# EMMC.net
KiCad netlist of a schematic drawn in Altium Designer
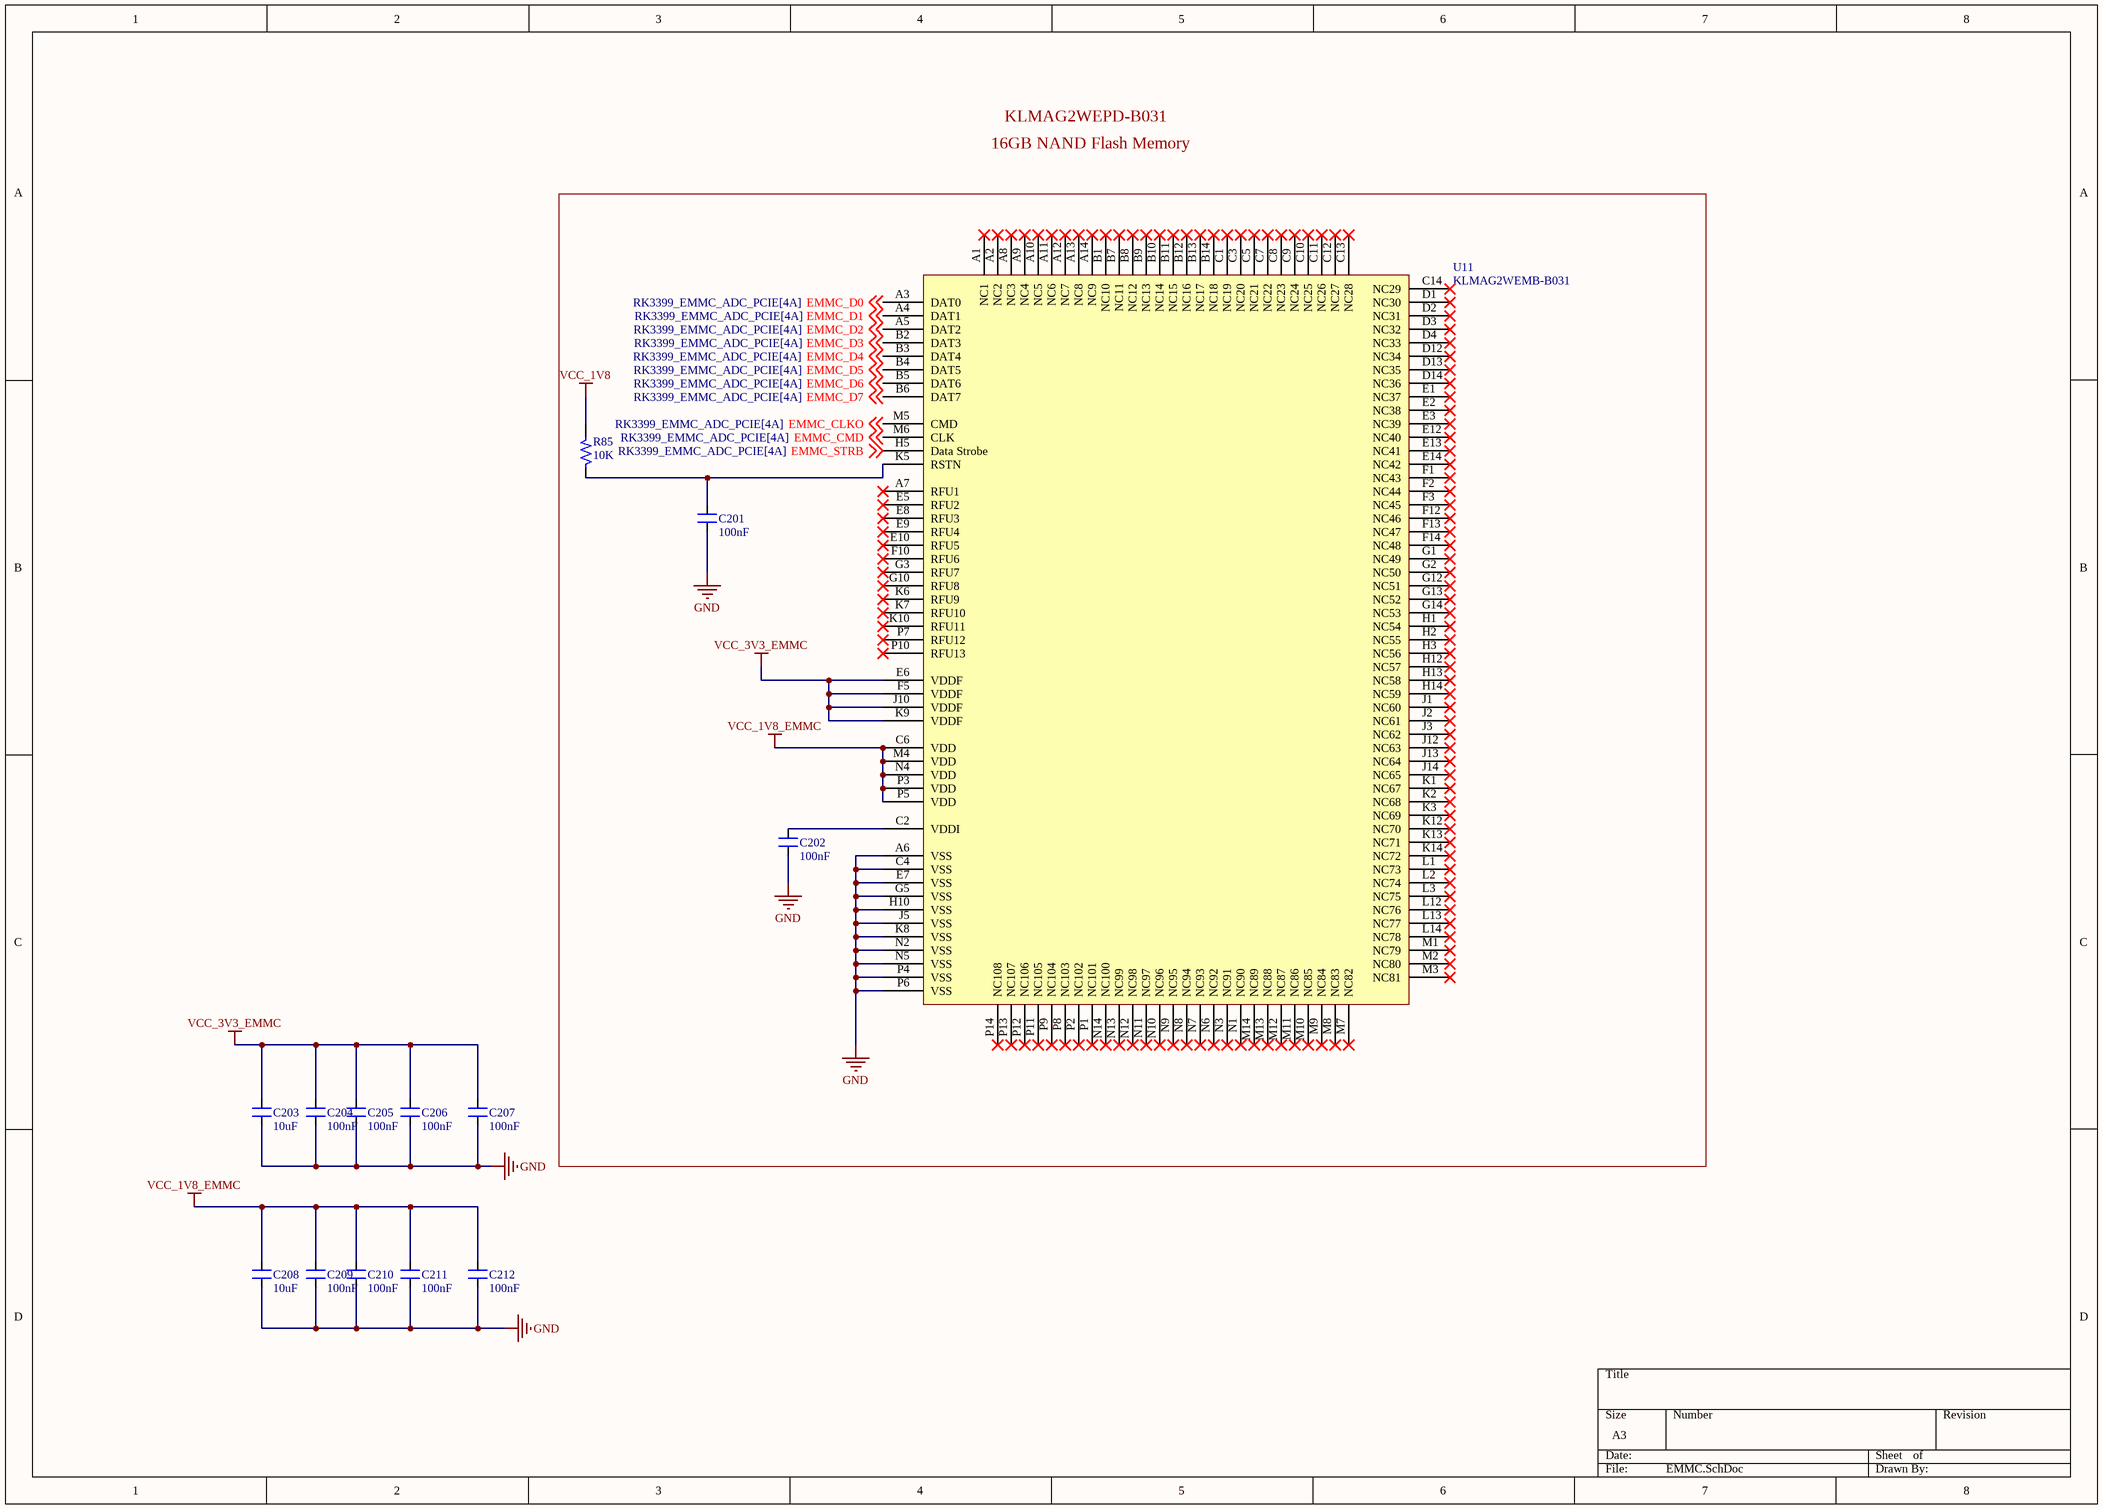
[diagram p0: EMMC.SchDoc]

(export (version "E")
  (design (tool "Eeschema 10.0.6"))
  (components
    (comp (ref "C201")
      (value "100nF")
      (footprint "CAP_0201")
      (description "0.1µF ±10% 25V Ceramic Capacitor X5R 0201 (0603 Metric)")
      (fields
        (field (name "MANUFACTURER") "TDK Corporation")
        (field (name "MANUFACTURER PART NUMBER") "C0603X5R1E104K030BB")
      )
      (libsource (lib "EsteemPCB_SOM_Course_schlib") (part "CAP_100nF-25V-10%-0201"))
    )
    (comp (ref "C202")
      (value "100nF")
      (footprint "CAP_0201")
      (description "0.1µF ±10% 25V Ceramic Capacitor X5R 0201 (0603 Metric)")
      (fields
        (field (name "MANUFACTURER") "TDK Corporation")
        (field (name "MANUFACTURER PART NUMBER") "C0603X5R1E104K030BB")
      )
      (libsource (lib "EsteemPCB_SOM_Course_schlib") (part "CAP_100nF-25V-10%-0201"))
    )
    (comp (ref "C203")
      (value "10uF")
      (footprint "CAP_0603")
      (description "10µF ±10% 10V Ceramic Capacitor X5R 0603 (1608 Metric)")
      (fields
        (field (name "MANUFACTURER PART NUMBER") "GRM188R61A106KE69J")
        (field (name "MANUFACTURER") "Murata Electronics")
      )
      (libsource (lib "EsteemPCB_SOM_Course_schlib") (part "CAP_10uF-10V-10%-0603"))
    )
    (comp (ref "C204")
      (value "100nF")
      (footprint "CAP_0201")
      (description "0.1µF ±10% 25V Ceramic Capacitor X5R 0201 (0603 Metric)")
      (fields
        (field (name "MANUFACTURER") "TDK Corporation")
        (field (name "MANUFACTURER PART NUMBER") "C0603X5R1E104K030BB")
      )
      (libsource (lib "EsteemPCB_SOM_Course_schlib") (part "CAP_100nF-25V-10%-0201"))
    )
    (comp (ref "C205")
      (value "100nF")
      (footprint "CAP_0201")
      (description "0.1µF ±10% 25V Ceramic Capacitor X5R 0201 (0603 Metric)")
      (fields
        (field (name "MANUFACTURER") "TDK Corporation")
        (field (name "MANUFACTURER PART NUMBER") "C0603X5R1E104K030BB")
      )
      (libsource (lib "EsteemPCB_SOM_Course_schlib") (part "CAP_100nF-25V-10%-0201"))
    )
    (comp (ref "C206")
      (value "100nF")
      (footprint "CAP_0201")
      (description "0.1µF ±10% 25V Ceramic Capacitor X5R 0201 (0603 Metric)")
      (fields
        (field (name "MANUFACTURER") "TDK Corporation")
        (field (name "MANUFACTURER PART NUMBER") "C0603X5R1E104K030BB")
      )
      (libsource (lib "EsteemPCB_SOM_Course_schlib") (part "CAP_100nF-25V-10%-0201"))
    )
    (comp (ref "C207")
      (value "100nF")
      (footprint "CAP_0201")
      (description "0.1µF ±10% 25V Ceramic Capacitor X5R 0201 (0603 Metric)")
      (fields
        (field (name "MANUFACTURER") "TDK Corporation")
        (field (name "MANUFACTURER PART NUMBER") "C0603X5R1E104K030BB")
      )
      (libsource (lib "EsteemPCB_SOM_Course_schlib") (part "CAP_100nF-25V-10%-0201"))
    )
    (comp (ref "C208")
      (value "10uF")
      (footprint "CAP_0603")
      (description "10µF ±10% 10V Ceramic Capacitor X5R 0603 (1608 Metric)")
      (fields
        (field (name "MANUFACTURER PART NUMBER") "GRM188R61A106KE69J")
        (field (name "MANUFACTURER") "Murata Electronics")
      )
      (libsource (lib "EsteemPCB_SOM_Course_schlib") (part "CAP_10uF-10V-10%-0603"))
    )
    (comp (ref "C209")
      (value "100nF")
      (footprint "CAP_0201")
      (description "0.1µF ±10% 25V Ceramic Capacitor X5R 0201 (0603 Metric)")
      (fields
        (field (name "MANUFACTURER") "TDK Corporation")
        (field (name "MANUFACTURER PART NUMBER") "C0603X5R1E104K030BB")
      )
      (libsource (lib "EsteemPCB_SOM_Course_schlib") (part "CAP_100nF-25V-10%-0201"))
    )
    (comp (ref "C210")
      (value "100nF")
      (footprint "CAP_0201")
      (description "0.1µF ±10% 25V Ceramic Capacitor X5R 0201 (0603 Metric)")
      (fields
        (field (name "MANUFACTURER") "TDK Corporation")
        (field (name "MANUFACTURER PART NUMBER") "C0603X5R1E104K030BB")
      )
      (libsource (lib "EsteemPCB_SOM_Course_schlib") (part "CAP_100nF-25V-10%-0201"))
    )
    (comp (ref "C211")
      (value "100nF")
      (footprint "CAP_0201")
      (description "0.1µF ±10% 25V Ceramic Capacitor X5R 0201 (0603 Metric)")
      (fields
        (field (name "MANUFACTURER") "TDK Corporation")
        (field (name "MANUFACTURER PART NUMBER") "C0603X5R1E104K030BB")
      )
      (libsource (lib "EsteemPCB_SOM_Course_schlib") (part "CAP_100nF-25V-10%-0201"))
    )
    (comp (ref "C212")
      (value "100nF")
      (footprint "CAP_0201")
      (description "0.1µF ±10% 25V Ceramic Capacitor X5R 0201 (0603 Metric)")
      (fields
        (field (name "MANUFACTURER") "TDK Corporation")
        (field (name "MANUFACTURER PART NUMBER") "C0603X5R1E104K030BB")
      )
      (libsource (lib "EsteemPCB_SOM_Course_schlib") (part "CAP_100nF-25V-10%-0201"))
    )
    (comp (ref "R85")
      (value "10K")
      (footprint "RES_0201")
      (description "10 kOhms ±1% 0.05W, 1/20W Chip Resistor 0201 (0603 Metric) Thick Film")
      (fields
        (field (name "MANUFACTURER") "Stackpole Electronics Inc")
        (field (name "MANUFACTURER PART NUMBER") "RMCF0201FT10K0")
      )
      (libsource (lib "EsteemPCB_SOM_Course_schlib") (part "RES_10K-0.05W-1%-0201"))
    )
    (comp (ref "U11")
      (value "KLMAG2WEMB-B031")
      (footprint "BGA153C50P14X14_1150X1300X70")
      (description "16GB NAND Flash Memory")
      (fields (field (name "MANUFACTURER") "Samsung Electronics"))
      (libsource (lib "EsteemPCB_SOM_Course_schlib") (part "IC_KLMAG2WEMB-B031"))
    )
  )
  (nets
    (net (code "1") (name "EMMC_CLKO") (class "Default")
      (node (ref "U11") (pin "M5") (pinfunction "CMD_M5") (pintype "passive"))
    )
    (net (code "2") (name "EMMC_CMD") (class "Default")
      (node (ref "U11") (pin "M6") (pinfunction "CLK_M6") (pintype "passive"))
    )
    (net (code "3") (name "EMMC_D0") (class "Default")
      (node (ref "U11") (pin "A3") (pinfunction "DAT0_A3") (pintype "passive"))
    )
    (net (code "4") (name "EMMC_D1") (class "Default")
      (node (ref "U11") (pin "A4") (pinfunction "DAT1_A4") (pintype "passive"))
    )
    (net (code "5") (name "EMMC_D2") (class "Default")
      (node (ref "U11") (pin "A5") (pinfunction "DAT2_A5") (pintype "passive"))
    )
    (net (code "6") (name "EMMC_D3") (class "Default")
      (node (ref "U11") (pin "B2") (pinfunction "DAT3_B2") (pintype "passive"))
    )
    (net (code "7") (name "EMMC_D4") (class "Default")
      (node (ref "U11") (pin "B3") (pinfunction "DAT4_B3") (pintype "passive"))
    )
    (net (code "8") (name "EMMC_D5") (class "Default")
      (node (ref "U11") (pin "B4") (pinfunction "DAT5_B4") (pintype "passive"))
    )
    (net (code "9") (name "EMMC_D6") (class "Default")
      (node (ref "U11") (pin "B5") (pinfunction "DAT6_B5") (pintype "passive"))
    )
    (net (code "10") (name "EMMC_D7") (class "Default")
      (node (ref "U11") (pin "B6") (pinfunction "DAT7_B6") (pintype "passive"))
    )
    (net (code "11") (name "EMMC_STRB") (class "Default")
      (node (ref "U11") (pin "H5") (pinfunction "Data_Strobe_H5") (pintype "passive"))
    )
    (net (code "12") (name "GND") (class "Default")
      (node (ref "C201") (pin "2") (pinfunction "2_2") (pintype "passive"))
      (node (ref "C202") (pin "2") (pinfunction "2_2") (pintype "passive"))
      (node (ref "C203") (pin "1") (pinfunction "1_1") (pintype "passive"))
      (node (ref "C204") (pin "2") (pinfunction "2_2") (pintype "passive"))
      (node (ref "C205") (pin "2") (pinfunction "2_2") (pintype "passive"))
      (node (ref "C206") (pin "2") (pinfunction "2_2") (pintype "passive"))
      (node (ref "C207") (pin "2") (pinfunction "2_2") (pintype "passive"))
      (node (ref "C208") (pin "1") (pinfunction "1_1") (pintype "passive"))
      (node (ref "C209") (pin "2") (pinfunction "2_2") (pintype "passive"))
      (node (ref "C210") (pin "2") (pinfunction "2_2") (pintype "passive"))
      (node (ref "C211") (pin "2") (pinfunction "2_2") (pintype "passive"))
      (node (ref "C212") (pin "2") (pinfunction "2_2") (pintype "passive"))
      (node (ref "U11") (pin "A6") (pinfunction "VSS_A6") (pintype "passive"))
      (node (ref "U11") (pin "C4") (pinfunction "VSS_C4") (pintype "passive"))
      (node (ref "U11") (pin "E7") (pinfunction "VSS_E7") (pintype "passive"))
      (node (ref "U11") (pin "G5") (pinfunction "VSS_G5") (pintype "passive"))
      (node (ref "U11") (pin "H10") (pinfunction "VSS_H10") (pintype "passive"))
      (node (ref "U11") (pin "J5") (pinfunction "VSS_J5") (pintype "passive"))
      (node (ref "U11") (pin "K8") (pinfunction "VSS_K8") (pintype "passive"))
      (node (ref "U11") (pin "N2") (pinfunction "VSS_N2") (pintype "passive"))
      (node (ref "U11") (pin "N5") (pinfunction "VSS_N5") (pintype "passive"))
      (node (ref "U11") (pin "P4") (pinfunction "VSS_P4") (pintype "passive"))
      (node (ref "U11") (pin "P6") (pinfunction "VSS_P6") (pintype "passive"))
    )
    (net (code "13") (name "Net-(U11-RSTN)") (class "Default")
      (node (ref "C201") (pin "1") (pinfunction "1_1") (pintype "passive"))
      (node (ref "R85") (pin "1") (pinfunction "1_1") (pintype "passive"))
      (node (ref "U11") (pin "K5") (pinfunction "RSTN_K5") (pintype "passive"))
    )
    (net (code "14") (name "Net-(U11-VDDI)") (class "Default")
      (node (ref "C202") (pin "1") (pinfunction "1_1") (pintype "passive"))
      (node (ref "U11") (pin "C2") (pinfunction "VDDI_C2") (pintype "passive"))
    )
    (net (code "15") (name "VCC_1V8") (class "Default")
      (node (ref "R85") (pin "2") (pinfunction "2_2") (pintype "passive"))
    )
    (net (code "16") (name "VCC_1V8_EMMC") (class "Default")
      (node (ref "C208") (pin "2") (pinfunction "2_2") (pintype "passive"))
      (node (ref "C209") (pin "1") (pinfunction "1_1") (pintype "passive"))
      (node (ref "C210") (pin "1") (pinfunction "1_1") (pintype "passive"))
      (node (ref "C211") (pin "1") (pinfunction "1_1") (pintype "passive"))
      (node (ref "C212") (pin "1") (pinfunction "1_1") (pintype "passive"))
      (node (ref "U11") (pin "C6") (pinfunction "VDD_C6") (pintype "passive"))
      (node (ref "U11") (pin "M4") (pinfunction "VDD_M4") (pintype "passive"))
      (node (ref "U11") (pin "N4") (pinfunction "VDD_N4") (pintype "passive"))
      (node (ref "U11") (pin "P3") (pinfunction "VDD_P3") (pintype "passive"))
      (node (ref "U11") (pin "P5") (pinfunction "VDD_P5") (pintype "passive"))
    )
    (net (code "17") (name "VCC_3V3_EMMC") (class "Default")
      (node (ref "C203") (pin "2") (pinfunction "2_2") (pintype "passive"))
      (node (ref "C204") (pin "1") (pinfunction "1_1") (pintype "passive"))
      (node (ref "C205") (pin "1") (pinfunction "1_1") (pintype "passive"))
      (node (ref "C206") (pin "1") (pinfunction "1_1") (pintype "passive"))
      (node (ref "C207") (pin "1") (pinfunction "1_1") (pintype "passive"))
      (node (ref "U11") (pin "E6") (pinfunction "VDDF_E6") (pintype "passive"))
      (node (ref "U11") (pin "F5") (pinfunction "VDDF_F5") (pintype "passive"))
      (node (ref "U11") (pin "J10") (pinfunction "VDDF_J10") (pintype "passive"))
      (node (ref "U11") (pin "K9") (pinfunction "VDDF_K9") (pintype "passive"))
    )
    (net (code "18") (name "unconnected-(U11-NC1-PadA1)") (class "Default")
      (node (ref "U11") (pin "A1") (pinfunction "NC1_A1") (pintype "passive+no_connect"))
    )
    (net (code "19") (name "unconnected-(U11-NC2-PadA2)") (class "Default")
      (node (ref "U11") (pin "A2") (pinfunction "NC2_A2") (pintype "passive+no_connect"))
    )
    (net (code "20") (name "unconnected-(U11-NC3-PadA8)") (class "Default")
      (node (ref "U11") (pin "A8") (pinfunction "NC3_A8") (pintype "passive+no_connect"))
    )
    (net (code "21") (name "unconnected-(U11-NC4-PadA9)") (class "Default")
      (node (ref "U11") (pin "A9") (pinfunction "NC4_A9") (pintype "passive+no_connect"))
    )
    (net (code "22") (name "unconnected-(U11-NC5-PadA10)") (class "Default")
      (node (ref "U11") (pin "A10") (pinfunction "NC5_A10") (pintype "passive+no_connect"))
    )
    (net (code "23") (name "unconnected-(U11-NC6-PadA11)") (class "Default")
      (node (ref "U11") (pin "A11") (pinfunction "NC6_A11") (pintype "passive+no_connect"))
    )
    (net (code "24") (name "unconnected-(U11-NC7-PadA12)") (class "Default")
      (node (ref "U11") (pin "A12") (pinfunction "NC7_A12") (pintype "passive+no_connect"))
    )
    (net (code "25") (name "unconnected-(U11-NC8-PadA13)") (class "Default")
      (node (ref "U11") (pin "A13") (pinfunction "NC8_A13") (pintype "passive+no_connect"))
    )
    (net (code "26") (name "unconnected-(U11-NC9-PadA14)") (class "Default")
      (node (ref "U11") (pin "A14") (pinfunction "NC9_A14") (pintype "passive+no_connect"))
    )
    (net (code "27") (name "unconnected-(U11-NC10-PadB1)") (class "Default")
      (node (ref "U11") (pin "B1") (pinfunction "NC10_B1") (pintype "passive+no_connect"))
    )
    (net (code "28") (name "unconnected-(U11-NC11-PadB7)") (class "Default")
      (node (ref "U11") (pin "B7") (pinfunction "NC11_B7") (pintype "passive+no_connect"))
    )
    (net (code "29") (name "unconnected-(U11-NC12-PadB8)") (class "Default")
      (node (ref "U11") (pin "B8") (pinfunction "NC12_B8") (pintype "passive+no_connect"))
    )
    (net (code "30") (name "unconnected-(U11-NC13-PadB9)") (class "Default")
      (node (ref "U11") (pin "B9") (pinfunction "NC13_B9") (pintype "passive+no_connect"))
    )
    (net (code "31") (name "unconnected-(U11-NC14-PadB10)") (class "Default")
      (node (ref "U11") (pin "B10") (pinfunction "NC14_B10") (pintype "passive+no_connect"))
    )
    (net (code "32") (name "unconnected-(U11-NC15-PadB11)") (class "Default")
      (node (ref "U11") (pin "B11") (pinfunction "NC15_B11") (pintype "passive+no_connect"))
    )
    (net (code "33") (name "unconnected-(U11-NC16-PadB12)") (class "Default")
      (node (ref "U11") (pin "B12") (pinfunction "NC16_B12") (pintype "passive+no_connect"))
    )
    (net (code "34") (name "unconnected-(U11-NC17-PadB13)") (class "Default")
      (node (ref "U11") (pin "B13") (pinfunction "NC17_B13") (pintype "passive+no_connect"))
    )
    (net (code "35") (name "unconnected-(U11-NC18-PadB14)") (class "Default")
      (node (ref "U11") (pin "B14") (pinfunction "NC18_B14") (pintype "passive+no_connect"))
    )
    (net (code "36") (name "unconnected-(U11-NC19-PadC1)") (class "Default")
      (node (ref "U11") (pin "C1") (pinfunction "NC19_C1") (pintype "passive+no_connect"))
    )
    (net (code "37") (name "unconnected-(U11-NC20-PadC3)") (class "Default")
      (node (ref "U11") (pin "C3") (pinfunction "NC20_C3") (pintype "passive+no_connect"))
    )
    (net (code "38") (name "unconnected-(U11-NC21-PadC5)") (class "Default")
      (node (ref "U11") (pin "C5") (pinfunction "NC21_C5") (pintype "passive+no_connect"))
    )
    (net (code "39") (name "unconnected-(U11-NC22-PadC7)") (class "Default")
      (node (ref "U11") (pin "C7") (pinfunction "NC22_C7") (pintype "passive+no_connect"))
    )
    (net (code "40") (name "unconnected-(U11-NC23-PadC8)") (class "Default")
      (node (ref "U11") (pin "C8") (pinfunction "NC23_C8") (pintype "passive+no_connect"))
    )
    (net (code "41") (name "unconnected-(U11-NC24-PadC9)") (class "Default")
      (node (ref "U11") (pin "C9") (pinfunction "NC24_C9") (pintype "passive+no_connect"))
    )
    (net (code "42") (name "unconnected-(U11-NC25-PadC10)") (class "Default")
      (node (ref "U11") (pin "C10") (pinfunction "NC25_C10") (pintype "passive+no_connect"))
    )
    (net (code "43") (name "unconnected-(U11-NC26-PadC11)") (class "Default")
      (node (ref "U11") (pin "C11") (pinfunction "NC26_C11") (pintype "passive+no_connect"))
    )
    (net (code "44") (name "unconnected-(U11-NC27-PadC12)") (class "Default")
      (node (ref "U11") (pin "C12") (pinfunction "NC27_C12") (pintype "passive+no_connect"))
    )
    (net (code "45") (name "unconnected-(U11-NC28-PadC13)") (class "Default")
      (node (ref "U11") (pin "C13") (pinfunction "NC28_C13") (pintype "passive+no_connect"))
    )
    (net (code "46") (name "unconnected-(U11-NC29-PadC14)") (class "Default")
      (node (ref "U11") (pin "C14") (pinfunction "NC29_C14") (pintype "passive+no_connect"))
    )
    (net (code "47") (name "unconnected-(U11-NC30-PadD1)") (class "Default")
      (node (ref "U11") (pin "D1") (pinfunction "NC30_D1") (pintype "passive+no_connect"))
    )
    (net (code "48") (name "unconnected-(U11-NC31-PadD2)") (class "Default")
      (node (ref "U11") (pin "D2") (pinfunction "NC31_D2") (pintype "passive+no_connect"))
    )
    (net (code "49") (name "unconnected-(U11-NC32-PadD3)") (class "Default")
      (node (ref "U11") (pin "D3") (pinfunction "NC32_D3") (pintype "passive+no_connect"))
    )
    (net (code "50") (name "unconnected-(U11-NC33-PadD4)") (class "Default")
      (node (ref "U11") (pin "D4") (pinfunction "NC33_D4") (pintype "passive+no_connect"))
    )
    (net (code "51") (name "unconnected-(U11-NC34-PadD12)") (class "Default")
      (node (ref "U11") (pin "D12") (pinfunction "NC34_D12") (pintype "passive+no_connect"))
    )
    (net (code "52") (name "unconnected-(U11-NC35-PadD13)") (class "Default")
      (node (ref "U11") (pin "D13") (pinfunction "NC35_D13") (pintype "passive+no_connect"))
    )
    (net (code "53") (name "unconnected-(U11-NC36-PadD14)") (class "Default")
      (node (ref "U11") (pin "D14") (pinfunction "NC36_D14") (pintype "passive+no_connect"))
    )
    (net (code "54") (name "unconnected-(U11-NC37-PadE1)") (class "Default")
      (node (ref "U11") (pin "E1") (pinfunction "NC37_E1") (pintype "passive+no_connect"))
    )
    (net (code "55") (name "unconnected-(U11-NC38-PadE2)") (class "Default")
      (node (ref "U11") (pin "E2") (pinfunction "NC38_E2") (pintype "passive+no_connect"))
    )
    (net (code "56") (name "unconnected-(U11-NC39-PadE3)") (class "Default")
      (node (ref "U11") (pin "E3") (pinfunction "NC39_E3") (pintype "passive+no_connect"))
    )
    (net (code "57") (name "unconnected-(U11-NC40-PadE12)") (class "Default")
      (node (ref "U11") (pin "E12") (pinfunction "NC40_E12") (pintype "passive+no_connect"))
    )
    (net (code "58") (name "unconnected-(U11-NC41-PadE13)") (class "Default")
      (node (ref "U11") (pin "E13") (pinfunction "NC41_E13") (pintype "passive+no_connect"))
    )
    (net (code "59") (name "unconnected-(U11-NC42-PadE14)") (class "Default")
      (node (ref "U11") (pin "E14") (pinfunction "NC42_E14") (pintype "passive+no_connect"))
    )
    (net (code "60") (name "unconnected-(U11-NC43-PadF1)") (class "Default")
      (node (ref "U11") (pin "F1") (pinfunction "NC43_F1") (pintype "passive+no_connect"))
    )
    (net (code "61") (name "unconnected-(U11-NC44-PadF2)") (class "Default")
      (node (ref "U11") (pin "F2") (pinfunction "NC44_F2") (pintype "passive+no_connect"))
    )
    (net (code "62") (name "unconnected-(U11-NC45-PadF3)") (class "Default")
      (node (ref "U11") (pin "F3") (pinfunction "NC45_F3") (pintype "passive+no_connect"))
    )
    (net (code "63") (name "unconnected-(U11-NC46-PadF12)") (class "Default")
      (node (ref "U11") (pin "F12") (pinfunction "NC46_F12") (pintype "passive+no_connect"))
    )
    (net (code "64") (name "unconnected-(U11-NC47-PadF13)") (class "Default")
      (node (ref "U11") (pin "F13") (pinfunction "NC47_F13") (pintype "passive+no_connect"))
    )
    (net (code "65") (name "unconnected-(U11-NC48-PadF14)") (class "Default")
      (node (ref "U11") (pin "F14") (pinfunction "NC48_F14") (pintype "passive+no_connect"))
    )
    (net (code "66") (name "unconnected-(U11-NC49-PadG1)") (class "Default")
      (node (ref "U11") (pin "G1") (pinfunction "NC49_G1") (pintype "passive+no_connect"))
    )
    (net (code "67") (name "unconnected-(U11-NC50-PadG2)") (class "Default")
      (node (ref "U11") (pin "G2") (pinfunction "NC50_G2") (pintype "passive+no_connect"))
    )
    (net (code "68") (name "unconnected-(U11-NC51-PadG12)") (class "Default")
      (node (ref "U11") (pin "G12") (pinfunction "NC51_G12") (pintype "passive+no_connect"))
    )
    (net (code "69") (name "unconnected-(U11-NC52-PadG13)") (class "Default")
      (node (ref "U11") (pin "G13") (pinfunction "NC52_G13") (pintype "passive+no_connect"))
    )
    (net (code "70") (name "unconnected-(U11-NC53-PadG14)") (class "Default")
      (node (ref "U11") (pin "G14") (pinfunction "NC53_G14") (pintype "passive+no_connect"))
    )
    (net (code "71") (name "unconnected-(U11-NC54-PadH1)") (class "Default")
      (node (ref "U11") (pin "H1") (pinfunction "NC54_H1") (pintype "passive+no_connect"))
    )
    (net (code "72") (name "unconnected-(U11-NC55-PadH2)") (class "Default")
      (node (ref "U11") (pin "H2") (pinfunction "NC55_H2") (pintype "passive+no_connect"))
    )
    (net (code "73") (name "unconnected-(U11-NC56-PadH3)") (class "Default")
      (node (ref "U11") (pin "H3") (pinfunction "NC56_H3") (pintype "passive+no_connect"))
    )
    (net (code "74") (name "unconnected-(U11-NC57-PadH12)") (class "Default")
      (node (ref "U11") (pin "H12") (pinfunction "NC57_H12") (pintype "passive+no_connect"))
    )
    (net (code "75") (name "unconnected-(U11-NC58-PadH13)") (class "Default")
      (node (ref "U11") (pin "H13") (pinfunction "NC58_H13") (pintype "passive+no_connect"))
    )
    (net (code "76") (name "unconnected-(U11-NC59-PadH14)") (class "Default")
      (node (ref "U11") (pin "H14") (pinfunction "NC59_H14") (pintype "passive+no_connect"))
    )
    (net (code "77") (name "unconnected-(U11-NC60-PadJ1)") (class "Default")
      (node (ref "U11") (pin "J1") (pinfunction "NC60_J1") (pintype "passive+no_connect"))
    )
    (net (code "78") (name "unconnected-(U11-NC61-PadJ2)") (class "Default")
      (node (ref "U11") (pin "J2") (pinfunction "NC61_J2") (pintype "passive+no_connect"))
    )
    (net (code "79") (name "unconnected-(U11-NC62-PadJ3)") (class "Default")
      (node (ref "U11") (pin "J3") (pinfunction "NC62_J3") (pintype "passive+no_connect"))
    )
    (net (code "80") (name "unconnected-(U11-NC63-PadJ12)") (class "Default")
      (node (ref "U11") (pin "J12") (pinfunction "NC63_J12") (pintype "passive+no_connect"))
    )
    (net (code "81") (name "unconnected-(U11-NC64-PadJ13)") (class "Default")
      (node (ref "U11") (pin "J13") (pinfunction "NC64_J13") (pintype "passive+no_connect"))
    )
    (net (code "82") (name "unconnected-(U11-NC65-PadJ14)") (class "Default")
      (node (ref "U11") (pin "J14") (pinfunction "NC65_J14") (pintype "passive+no_connect"))
    )
    (net (code "83") (name "unconnected-(U11-NC67-PadK1)") (class "Default")
      (node (ref "U11") (pin "K1") (pinfunction "NC67_K1") (pintype "passive+no_connect"))
    )
    (net (code "84") (name "unconnected-(U11-NC68-PadK2)") (class "Default")
      (node (ref "U11") (pin "K2") (pinfunction "NC68_K2") (pintype "passive+no_connect"))
    )
    (net (code "85") (name "unconnected-(U11-NC69-PadK3)") (class "Default")
      (node (ref "U11") (pin "K3") (pinfunction "NC69_K3") (pintype "passive+no_connect"))
    )
    (net (code "86") (name "unconnected-(U11-NC70-PadK12)") (class "Default")
      (node (ref "U11") (pin "K12") (pinfunction "NC70_K12") (pintype "passive+no_connect"))
    )
    (net (code "87") (name "unconnected-(U11-NC71-PadK13)") (class "Default")
      (node (ref "U11") (pin "K13") (pinfunction "NC71_K13") (pintype "passive+no_connect"))
    )
    (net (code "88") (name "unconnected-(U11-NC72-PadK14)") (class "Default")
      (node (ref "U11") (pin "K14") (pinfunction "NC72_K14") (pintype "passive+no_connect"))
    )
    (net (code "89") (name "unconnected-(U11-NC73-PadL1)") (class "Default")
      (node (ref "U11") (pin "L1") (pinfunction "NC73_L1") (pintype "passive+no_connect"))
    )
    (net (code "90") (name "unconnected-(U11-NC74-PadL2)") (class "Default")
      (node (ref "U11") (pin "L2") (pinfunction "NC74_L2") (pintype "passive+no_connect"))
    )
    (net (code "91") (name "unconnected-(U11-NC75-PadL3)") (class "Default")
      (node (ref "U11") (pin "L3") (pinfunction "NC75_L3") (pintype "passive+no_connect"))
    )
    (net (code "92") (name "unconnected-(U11-NC76-PadL12)") (class "Default")
      (node (ref "U11") (pin "L12") (pinfunction "NC76_L12") (pintype "passive+no_connect"))
    )
    (net (code "93") (name "unconnected-(U11-NC77-PadL13)") (class "Default")
      (node (ref "U11") (pin "L13") (pinfunction "NC77_L13") (pintype "passive+no_connect"))
    )
    (net (code "94") (name "unconnected-(U11-NC78-PadL14)") (class "Default")
      (node (ref "U11") (pin "L14") (pinfunction "NC78_L14") (pintype "passive+no_connect"))
    )
    (net (code "95") (name "unconnected-(U11-NC79-PadM1)") (class "Default")
      (node (ref "U11") (pin "M1") (pinfunction "NC79_M1") (pintype "passive+no_connect"))
    )
    (net (code "96") (name "unconnected-(U11-NC80-PadM2)") (class "Default")
      (node (ref "U11") (pin "M2") (pinfunction "NC80_M2") (pintype "passive+no_connect"))
    )
    (net (code "97") (name "unconnected-(U11-NC81-PadM3)") (class "Default")
      (node (ref "U11") (pin "M3") (pinfunction "NC81_M3") (pintype "passive+no_connect"))
    )
    (net (code "98") (name "unconnected-(U11-NC82-PadM7)") (class "Default")
      (node (ref "U11") (pin "M7") (pinfunction "NC82_M7") (pintype "passive+no_connect"))
    )
    (net (code "99") (name "unconnected-(U11-NC83-PadM8)") (class "Default")
      (node (ref "U11") (pin "M8") (pinfunction "NC83_M8") (pintype "passive+no_connect"))
    )
    (net (code "100") (name "unconnected-(U11-NC84-PadM9)") (class "Default")
      (node (ref "U11") (pin "M9") (pinfunction "NC84_M9") (pintype "passive+no_connect"))
    )
    (net (code "101") (name "unconnected-(U11-NC85-PadM10)") (class "Default")
      (node (ref "U11") (pin "M10") (pinfunction "NC85_M10") (pintype "passive+no_connect"))
    )
    (net (code "102") (name "unconnected-(U11-NC86-PadM11)") (class "Default")
      (node (ref "U11") (pin "M11") (pinfunction "NC86_M11") (pintype "passive+no_connect"))
    )
    (net (code "103") (name "unconnected-(U11-NC87-PadM12)") (class "Default")
      (node (ref "U11") (pin "M12") (pinfunction "NC87_M12") (pintype "passive+no_connect"))
    )
    (net (code "104") (name "unconnected-(U11-NC88-PadM13)") (class "Default")
      (node (ref "U11") (pin "M13") (pinfunction "NC88_M13") (pintype "passive+no_connect"))
    )
    (net (code "105") (name "unconnected-(U11-NC89-PadM14)") (class "Default")
      (node (ref "U11") (pin "M14") (pinfunction "NC89_M14") (pintype "passive+no_connect"))
    )
    (net (code "106") (name "unconnected-(U11-NC90-PadN1)") (class "Default")
      (node (ref "U11") (pin "N1") (pinfunction "NC90_N1") (pintype "passive+no_connect"))
    )
    (net (code "107") (name "unconnected-(U11-NC91-PadN3)") (class "Default")
      (node (ref "U11") (pin "N3") (pinfunction "NC91_N3") (pintype "passive+no_connect"))
    )
    (net (code "108") (name "unconnected-(U11-NC92-PadN6)") (class "Default")
      (node (ref "U11") (pin "N6") (pinfunction "NC92_N6") (pintype "passive+no_connect"))
    )
    (net (code "109") (name "unconnected-(U11-NC93-PadN7)") (class "Default")
      (node (ref "U11") (pin "N7") (pinfunction "NC93_N7") (pintype "passive+no_connect"))
    )
    (net (code "110") (name "unconnected-(U11-NC94-PadN8)") (class "Default")
      (node (ref "U11") (pin "N8") (pinfunction "NC94_N8") (pintype "passive+no_connect"))
    )
    (net (code "111") (name "unconnected-(U11-NC95-PadN9)") (class "Default")
      (node (ref "U11") (pin "N9") (pinfunction "NC95_N9") (pintype "passive+no_connect"))
    )
    (net (code "112") (name "unconnected-(U11-NC96-PadN10)") (class "Default")
      (node (ref "U11") (pin "N10") (pinfunction "NC96_N10") (pintype "passive+no_connect"))
    )
    (net (code "113") (name "unconnected-(U11-NC97-PadN11)") (class "Default")
      (node (ref "U11") (pin "N11") (pinfunction "NC97_N11") (pintype "passive+no_connect"))
    )
    (net (code "114") (name "unconnected-(U11-NC98-PadN12)") (class "Default")
      (node (ref "U11") (pin "N12") (pinfunction "NC98_N12") (pintype "passive+no_connect"))
    )
    (net (code "115") (name "unconnected-(U11-NC99-PadN13)") (class "Default")
      (node (ref "U11") (pin "N13") (pinfunction "NC99_N13") (pintype "passive+no_connect"))
    )
    (net (code "116") (name "unconnected-(U11-NC100-PadN14)") (class "Default")
      (node (ref "U11") (pin "N14") (pinfunction "NC100_N14") (pintype "passive+no_connect"))
    )
    (net (code "117") (name "unconnected-(U11-NC101-PadP1)") (class "Default")
      (node (ref "U11") (pin "P1") (pinfunction "NC101_P1") (pintype "passive+no_connect"))
    )
    (net (code "118") (name "unconnected-(U11-NC102-PadP2)") (class "Default")
      (node (ref "U11") (pin "P2") (pinfunction "NC102_P2") (pintype "passive+no_connect"))
    )
    (net (code "119") (name "unconnected-(U11-NC103-PadP8)") (class "Default")
      (node (ref "U11") (pin "P8") (pinfunction "NC103_P8") (pintype "passive+no_connect"))
    )
    (net (code "120") (name "unconnected-(U11-NC104-PadP9)") (class "Default")
      (node (ref "U11") (pin "P9") (pinfunction "NC104_P9") (pintype "passive+no_connect"))
    )
    (net (code "121") (name "unconnected-(U11-NC105-PadP11)") (class "Default")
      (node (ref "U11") (pin "P11") (pinfunction "NC105_P11") (pintype "passive+no_connect"))
    )
    (net (code "122") (name "unconnected-(U11-NC106-PadP12)") (class "Default")
      (node (ref "U11") (pin "P12") (pinfunction "NC106_P12") (pintype "passive+no_connect"))
    )
    (net (code "123") (name "unconnected-(U11-NC107-PadP13)") (class "Default")
      (node (ref "U11") (pin "P13") (pinfunction "NC107_P13") (pintype "passive+no_connect"))
    )
    (net (code "124") (name "unconnected-(U11-NC108-PadP14)") (class "Default")
      (node (ref "U11") (pin "P14") (pinfunction "NC108_P14") (pintype "passive+no_connect"))
    )
    (net (code "125") (name "unconnected-(U11-RFU1-PadA7)") (class "Default")
      (node (ref "U11") (pin "A7") (pinfunction "RFU1_A7") (pintype "passive+no_connect"))
    )
    (net (code "126") (name "unconnected-(U11-RFU2-PadE5)") (class "Default")
      (node (ref "U11") (pin "E5") (pinfunction "RFU2_E5") (pintype "passive+no_connect"))
    )
    (net (code "127") (name "unconnected-(U11-RFU3-PadE8)") (class "Default")
      (node (ref "U11") (pin "E8") (pinfunction "RFU3_E8") (pintype "passive+no_connect"))
    )
    (net (code "128") (name "unconnected-(U11-RFU4-PadE9)") (class "Default")
      (node (ref "U11") (pin "E9") (pinfunction "RFU4_E9") (pintype "passive+no_connect"))
    )
    (net (code "129") (name "unconnected-(U11-RFU5-PadE10)") (class "Default")
      (node (ref "U11") (pin "E10") (pinfunction "RFU5_E10") (pintype "passive+no_connect"))
    )
    (net (code "130") (name "unconnected-(U11-RFU6-PadF10)") (class "Default")
      (node (ref "U11") (pin "F10") (pinfunction "RFU6_F10") (pintype "passive+no_connect"))
    )
    (net (code "131") (name "unconnected-(U11-RFU7-PadG3)") (class "Default")
      (node (ref "U11") (pin "G3") (pinfunction "RFU7_G3") (pintype "passive+no_connect"))
    )
    (net (code "132") (name "unconnected-(U11-RFU8-PadG10)") (class "Default")
      (node (ref "U11") (pin "G10") (pinfunction "RFU8_G10") (pintype "passive+no_connect"))
    )
    (net (code "133") (name "unconnected-(U11-RFU9-PadK6)") (class "Default")
      (node (ref "U11") (pin "K6") (pinfunction "RFU9_K6") (pintype "passive+no_connect"))
    )
    (net (code "134") (name "unconnected-(U11-RFU10-PadK7)") (class "Default")
      (node (ref "U11") (pin "K7") (pinfunction "RFU10_K7") (pintype "passive+no_connect"))
    )
    (net (code "135") (name "unconnected-(U11-RFU11-PadK10)") (class "Default")
      (node (ref "U11") (pin "K10") (pinfunction "RFU11_K10") (pintype "passive+no_connect"))
    )
    (net (code "136") (name "unconnected-(U11-RFU12-PadP7)") (class "Default")
      (node (ref "U11") (pin "P7") (pinfunction "RFU12_P7") (pintype "passive+no_connect"))
    )
    (net (code "137") (name "unconnected-(U11-RFU13-PadP10)") (class "Default")
      (node (ref "U11") (pin "P10") (pinfunction "RFU13_P10") (pintype "passive+no_connect"))
    )
  )
)
